# PCB-2__SCH_PHOENIX.net
KiCad netlist of a schematic drawn in EasyEDA
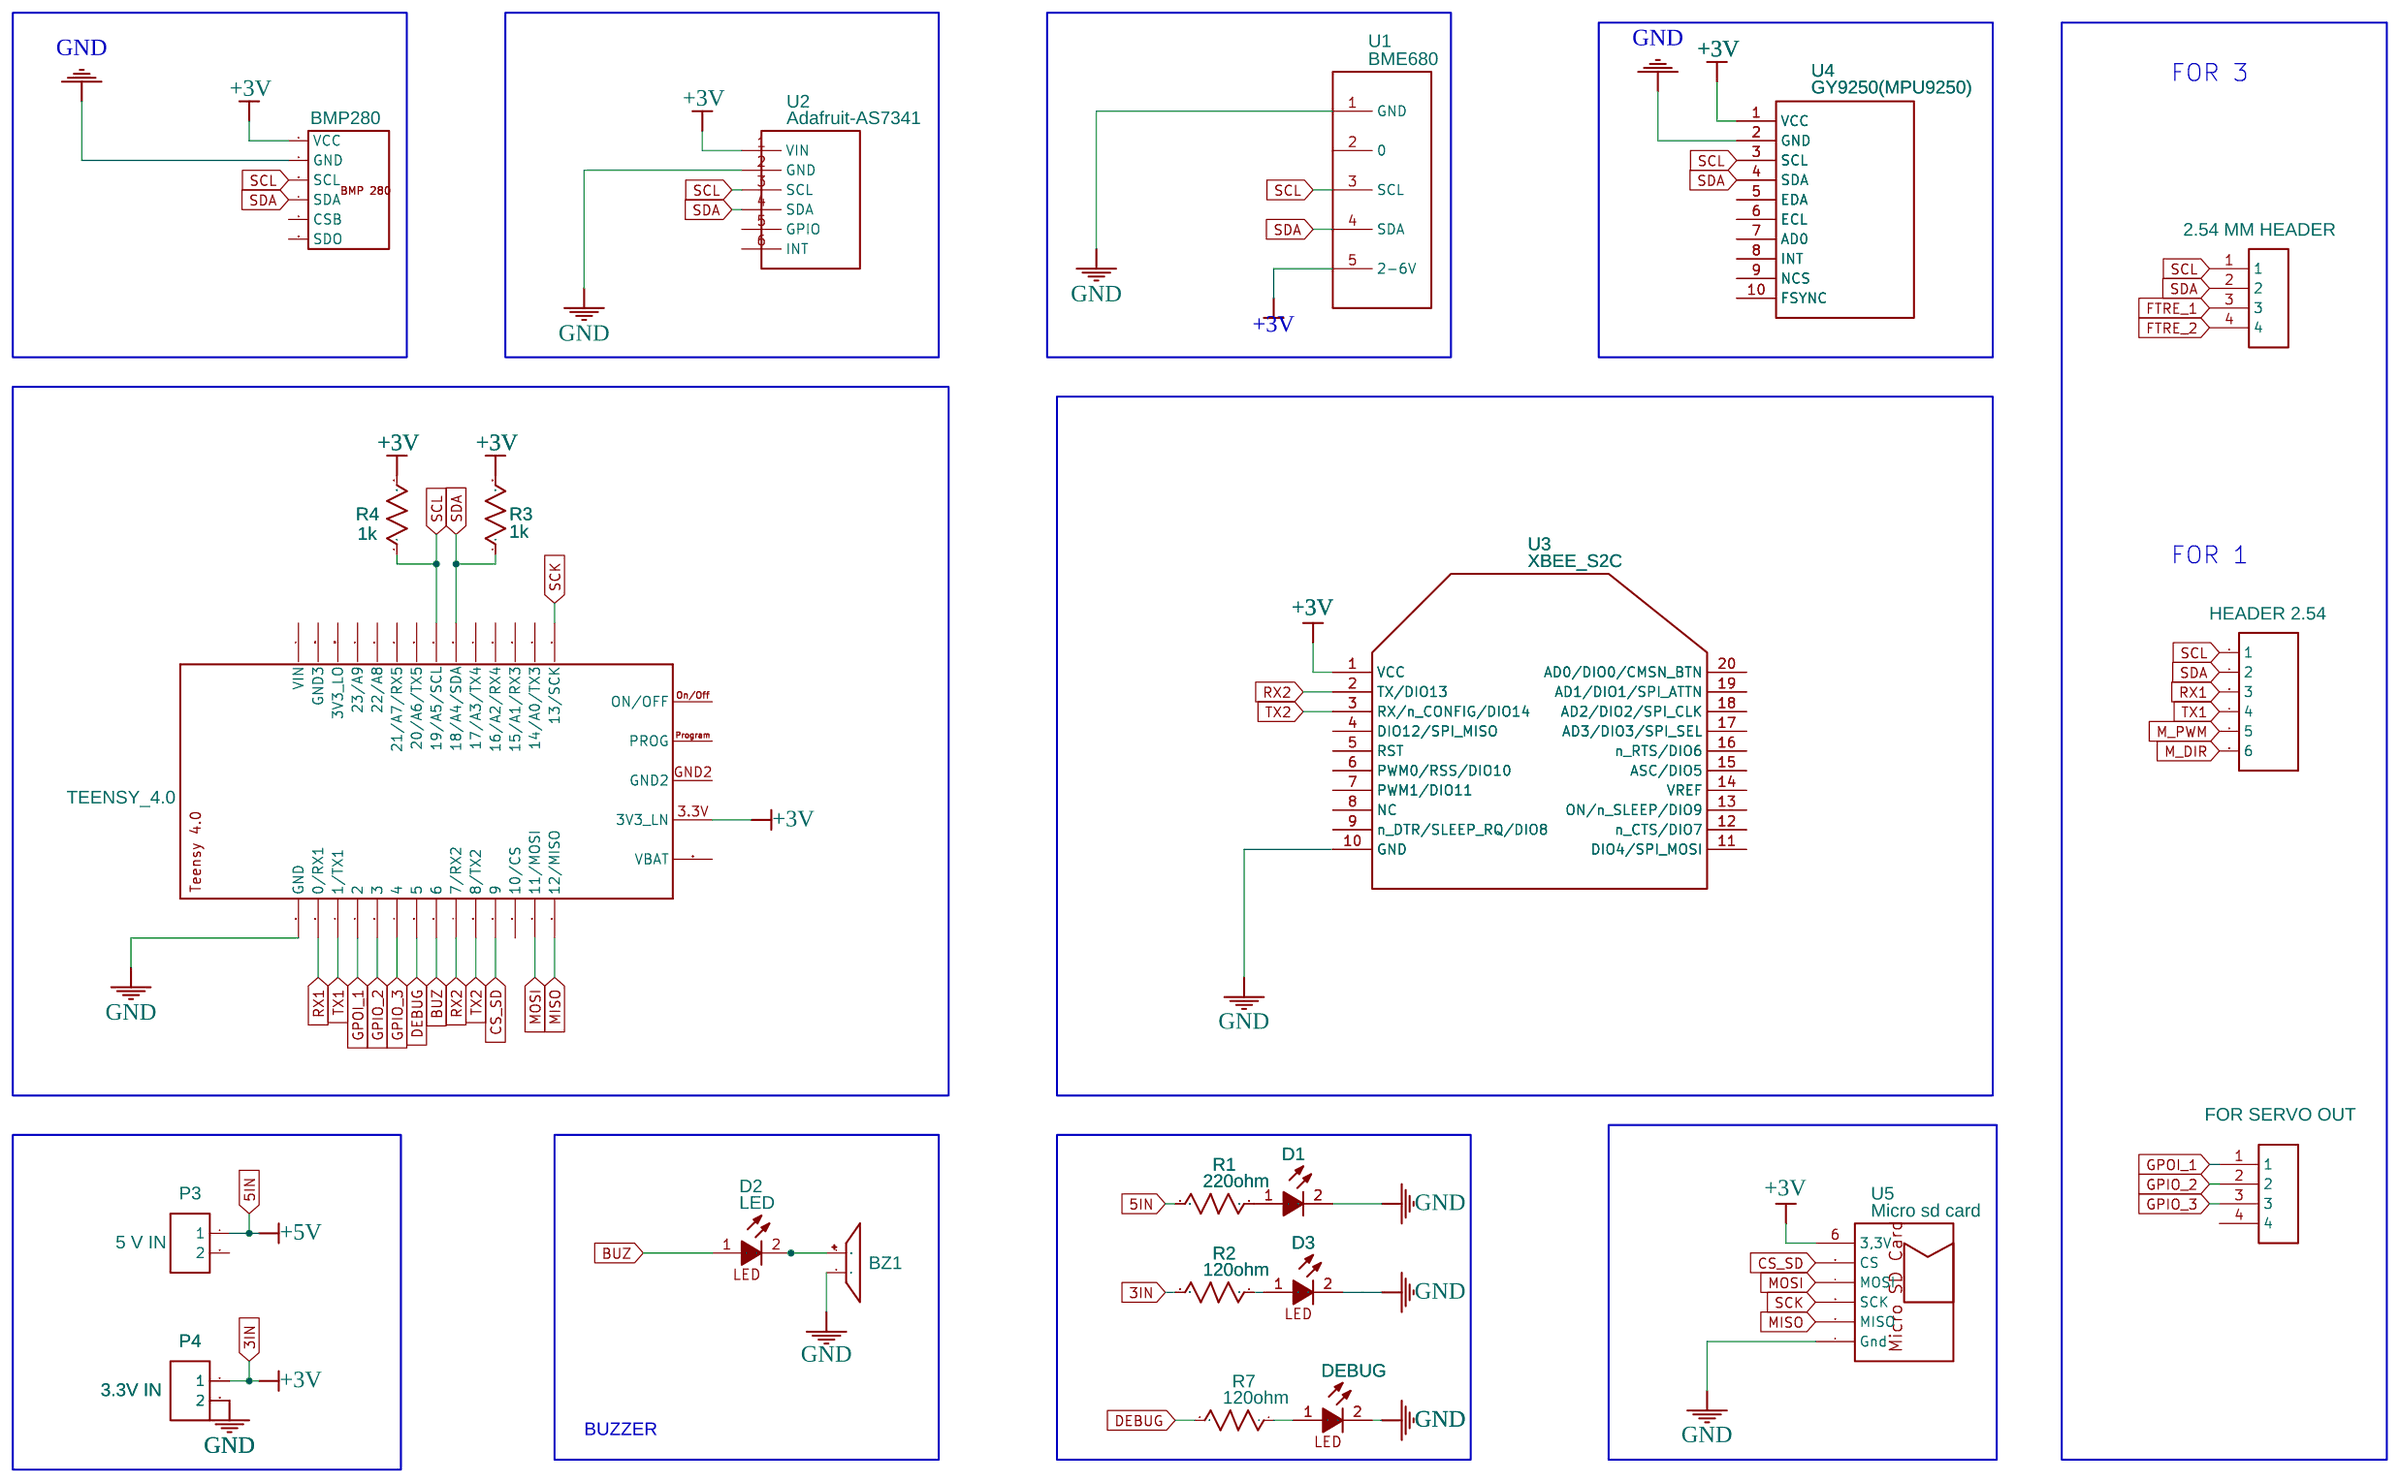
[diagram p0: schematic sheet]

(export (version "E")
  (design (tool "Eeschema 10.0.6"))
  (components
    (comp (ref "0") (value "TEENSY_4.0") (libsource (lib "") (part "TEENSY_4.0")))
    (comp (ref "BZ1") (value "Buzzer") (libsource (lib "") (part "Buzzer")))
    (comp (ref "D1")
      (value "LED")
      (fields (field (name "Manufacturer Part") "5600") (field (name "Manufacturer") "VccLite"))
      (libsource (lib "") (part "LED_1"))
    )
    (comp (ref "D2")
      (value "LED")
      (fields (field (name "Manufacturer Part") "5600") (field (name "Manufacturer") "VccLite"))
      (libsource (lib "") (part "LED_2"))
    )
    (comp (ref "D3")
      (value "LED")
      (fields (field (name "Manufacturer Part") "5600") (field (name "Manufacturer") "VccLite"))
      (libsource (lib "") (part "LED_2"))
    )
    (comp (ref "DEBUG")
      (value "LED")
      (fields (field (name "Manufacturer Part") "5600") (field (name "Manufacturer") "VccLite"))
      (libsource (lib "") (part "LED"))
    )
    (comp (ref "H1")
      (value "2.54 MM HEADER")
      (fields (field (name "Manufacturer Part") "2211S-04G") (field (name "Manufacturer") "MULTICOMP PRO"))
      (libsource (lib "") (part "B2B 2.54 MM HEADER"))
    )
    (comp (ref "H2")
      (value "FOR SERVO OUT")
      (fields (field (name "Manufacturer Part") "2211S-04G") (field (name "Manufacturer") "MULTICOMP PRO"))
      (libsource (lib "") (part "B2B 2.54 MM HEADER"))
    )
    (comp (ref "J1")
      (value "HEADER 2.54")
      (fields (field (name "Manufacturer Part") "2.54mm 1*20PHeader"))
      (libsource (lib "") (part "HEADER-MALE-2.54_1X6"))
    )
    (comp (ref "MOD1") (value "BMP280") (libsource (lib "") (part "BMP280")))
    (comp (ref "P3") (value "5 V IN") (libsource (lib "") (part "CONN-TH_2P-P5.00")))
    (comp (ref "P4") (value "3.3V IN") (libsource (lib "") (part "CONN-TH_2P-P5.00")))
    (comp (ref "R1") (value "220ohm") (libsource (lib "") (part "R_0603_US")))
    (comp (ref "R2") (value "120ohm") (libsource (lib "") (part "R_0603_US")))
    (comp (ref "R3") (value "1k") (libsource (lib "") (part "R_0603_US_1")))
    (comp (ref "R4") (value "1k") (libsource (lib "") (part "R_0603_US_1")))
    (comp (ref "R7") (value "120ohm") (libsource (lib "") (part "R_0603_US")))
    (comp (ref "U1") (value "BME680") (libsource (lib "") (part "BME680")))
    (comp (ref "U2") (value "Adafruit-AS7341") (libsource (lib "") (part "Adafruit-AS7341")))
    (comp (ref "U3")
      (value "XBEE_S2C")
      (fields
        (field (name "Manufacturer Part") "XBP24CZ7PITB003")
        (field (name "Manufacturer") "Digi International")
      )
      (libsource (lib "") (part "XBEE_S2C"))
    )
    (comp (ref "U4") (value "GY9250(MPU9250)") (libsource (lib "") (part "GY9250(MPU9250)")))
    (comp (ref "U5")
      (value "Micro sd card")
      (fields (field (name "Manufacturer Part") "Micro sd card module"))
      (libsource (lib "") (part "Micro sd card module"))
    )
  )
  (nets
    (net (code "1") (name "3IN") (class "Default")
      (node (ref "0") (pin "3.3V") (pinfunction "3V3_LN_3.3V") (pintype "bidirectional"))
      (node (ref "MOD1") (pin "1") (pinfunction "VCC_1") (pintype "unspecified"))
      (node (ref "P4") (pin "1") (pinfunction "1_1") (pintype "unspecified"))
      (node (ref "R2") (pin "2") (pinfunction "2_2") (pintype "unspecified"))
      (node (ref "R3") (pin "2") (pinfunction "2_2") (pintype "unspecified"))
      (node (ref "R4") (pin "2") (pinfunction "2_2") (pintype "unspecified"))
      (node (ref "U1") (pin "5") (pinfunction "2-6V_5") (pintype "passive"))
      (node (ref "U2") (pin "1") (pinfunction "VIN_1") (pintype "unspecified"))
      (node (ref "U3") (pin "1") (pinfunction "VCC_1") (pintype "passive"))
      (node (ref "U4") (pin "1") (pinfunction "VCC_1") (pintype "unspecified"))
      (node (ref "U5") (pin "6") (pinfunction "3,3V_6") (pintype "unspecified"))
    )
    (net (code "2") (name "5IN") (class "Default")
      (node (ref "P3") (pin "1") (pinfunction "1_1") (pintype "unspecified"))
      (node (ref "R1") (pin "2") (pinfunction "2_2") (pintype "unspecified"))
    )
    (net (code "3") (name "BUZ") (class "Default")
      (node (ref "0") (pin "6") (pinfunction "6_6") (pintype "bidirectional"))
      (node (ref "D2") (pin "1") (pinfunction "A_1") (pintype "unspecified"))
    )
    (net (code "4") (name "CS_SD") (class "Default")
      (node (ref "0") (pin "9") (pinfunction "9_9") (pintype "bidirectional"))
      (node (ref "U5") (pin "5") (pinfunction "CS_5") (pintype "unspecified"))
    )
    (net (code "5") (name "DEBUG") (class "Default")
      (node (ref "0") (pin "5") (pinfunction "5_5") (pintype "bidirectional"))
      (node (ref "R7") (pin "2") (pinfunction "2_2") (pintype "unspecified"))
    )
    (net (code "6") (name "FTRE_1") (class "Default")
      (node (ref "H1") (pin "3") (pinfunction "3_3") (pintype "unspecified"))
    )
    (net (code "7") (name "FTRE_2") (class "Default")
      (node (ref "H1") (pin "4") (pinfunction "4_4") (pintype "unspecified"))
    )
    (net (code "8") (name "GND") (class "Default")
      (node (ref "0") (pin "GND1") (pinfunction "GND_GND1") (pintype "bidirectional"))
      (node (ref "BZ1") (pin "2") (pinfunction "2_2") (pintype "unspecified"))
      (node (ref "D1") (pin "2") (pinfunction "K_2") (pintype "unspecified"))
      (node (ref "D3") (pin "2") (pinfunction "K_2") (pintype "unspecified"))
      (node (ref "DEBUG") (pin "2") (pinfunction "K_2") (pintype "unspecified"))
      (node (ref "MOD1") (pin "2") (pinfunction "GND_2") (pintype "unspecified"))
      (node (ref "P4") (pin "2") (pinfunction "2_2") (pintype "unspecified"))
      (node (ref "U1") (pin "1") (pinfunction "GND_1") (pintype "passive"))
      (node (ref "U2") (pin "2") (pinfunction "GND_2") (pintype "unspecified"))
      (node (ref "U3") (pin "10") (pinfunction "GND_10") (pintype "passive"))
      (node (ref "U4") (pin "2") (pinfunction "GND_2") (pintype "unspecified"))
      (node (ref "U5") (pin "1") (pinfunction "Gnd_1") (pintype "unspecified"))
    )
    (net (code "9") (name "GPIO_2") (class "Default")
      (node (ref "0") (pin "3") (pinfunction "3_3") (pintype "bidirectional"))
      (node (ref "H2") (pin "2") (pinfunction "2_2") (pintype "unspecified"))
    )
    (net (code "10") (name "GPIO_3") (class "Default")
      (node (ref "0") (pin "4") (pinfunction "4_4") (pintype "bidirectional"))
      (node (ref "H2") (pin "3") (pinfunction "3_3") (pintype "unspecified"))
    )
    (net (code "11") (name "GPOI_1") (class "Default")
      (node (ref "0") (pin "2") (pinfunction "2_2") (pintype "bidirectional"))
      (node (ref "H2") (pin "1") (pinfunction "1_1") (pintype "unspecified"))
    )
    (net (code "12") (name "MISO") (class "Default")
      (node (ref "0") (pin "12") (pinfunction "12/MISO_12") (pintype "bidirectional"))
      (node (ref "U5") (pin "2") (pinfunction "MISO_2") (pintype "unspecified"))
    )
    (net (code "13") (name "MOSI") (class "Default")
      (node (ref "0") (pin "11") (pinfunction "11/MOSI_11") (pintype "bidirectional"))
      (node (ref "U5") (pin "4") (pinfunction "MOSI_4") (pintype "unspecified"))
    )
    (net (code "14") (name "M_DIR") (class "Default")
      (node (ref "J1") (pin "6") (pinfunction "6_6") (pintype "input"))
    )
    (net (code "15") (name "M_PWM") (class "Default")
      (node (ref "J1") (pin "5") (pinfunction "5_5") (pintype "input"))
    )
    (net (code "16") (name "Net-(BZ1-Buzzer)") (class "Default")
      (node (ref "BZ1") (pin "1") (pinfunction "Buzzer_1") (pintype "unspecified"))
      (node (ref "D2") (pin "2") (pinfunction "K_2") (pintype "unspecified"))
    )
    (net (code "17") (name "Net-(D1-A)") (class "Default")
      (node (ref "D1") (pin "1") (pinfunction "A_1") (pintype "unspecified"))
      (node (ref "R1") (pin "1") (pinfunction "1_1") (pintype "unspecified"))
    )
    (net (code "18") (name "Net-(D3-A)") (class "Default")
      (node (ref "D3") (pin "1") (pinfunction "A_1") (pintype "unspecified"))
      (node (ref "R2") (pin "1") (pinfunction "1_1") (pintype "unspecified"))
    )
    (net (code "19") (name "Net-(DEBUG-A)") (class "Default")
      (node (ref "DEBUG") (pin "1") (pinfunction "A_1") (pintype "unspecified"))
      (node (ref "R7") (pin "1") (pinfunction "1_1") (pintype "unspecified"))
    )
    (net (code "20") (name "RX1") (class "Default")
      (node (ref "0") (pin "0") (pinfunction "0/RX1_0") (pintype "bidirectional"))
      (node (ref "J1") (pin "3") (pinfunction "3_3") (pintype "input"))
    )
    (net (code "21") (name "RX2") (class "Default")
      (node (ref "0") (pin "7") (pinfunction "7/RX2_7") (pintype "bidirectional"))
      (node (ref "U3") (pin "2") (pinfunction "TX/DIO13_2") (pintype "output"))
    )
    (net (code "22") (name "SCK") (class "Default")
      (node (ref "0") (pin "13") (pinfunction "13/SCK_13") (pintype "bidirectional"))
      (node (ref "U5") (pin "3") (pinfunction "SCK_3") (pintype "unspecified"))
    )
    (net (code "23") (name "SCL") (class "Default")
      (node (ref "0") (pin "19") (pinfunction "19/A5/SCL_19") (pintype "bidirectional"))
      (node (ref "H1") (pin "1") (pinfunction "1_1") (pintype "unspecified"))
      (node (ref "J1") (pin "1") (pinfunction "1_1") (pintype "input"))
      (node (ref "MOD1") (pin "3") (pinfunction "SCL_3") (pintype "unspecified"))
      (node (ref "R4") (pin "1") (pinfunction "1_1") (pintype "unspecified"))
      (node (ref "U1") (pin "3") (pinfunction "SCL_3") (pintype "bidirectional"))
      (node (ref "U2") (pin "3") (pinfunction "SCL_3") (pintype "unspecified"))
      (node (ref "U4") (pin "3") (pinfunction "SCL_3") (pintype "unspecified"))
    )
    (net (code "24") (name "SDA") (class "Default")
      (node (ref "0") (pin "18") (pinfunction "18/A4/SDA_18") (pintype "bidirectional"))
      (node (ref "H1") (pin "2") (pinfunction "2_2") (pintype "unspecified"))
      (node (ref "J1") (pin "2") (pinfunction "2_2") (pintype "input"))
      (node (ref "MOD1") (pin "4") (pinfunction "SDA_4") (pintype "unspecified"))
      (node (ref "R3") (pin "1") (pinfunction "1_1") (pintype "unspecified"))
      (node (ref "U1") (pin "4") (pinfunction "SDA_4") (pintype "bidirectional"))
      (node (ref "U2") (pin "4") (pinfunction "SDA_4") (pintype "unspecified"))
      (node (ref "U4") (pin "4") (pinfunction "SDA_4") (pintype "unspecified"))
    )
    (net (code "25") (name "TX1") (class "Default")
      (node (ref "0") (pin "1") (pinfunction "1/TX1_1") (pintype "bidirectional"))
      (node (ref "J1") (pin "4") (pinfunction "4_4") (pintype "input"))
    )
    (net (code "26") (name "TX2") (class "Default")
      (node (ref "0") (pin "8") (pinfunction "8/TX2_8") (pintype "bidirectional"))
      (node (ref "U3") (pin "3") (pinfunction "RX/n_CONFIG/DIO14_3") (pintype "input"))
    )
    (net (code "27") (name "unconnected-(0-3V3_LO-Pad3.3V{slash}250)") (class "Default")
      (node (ref "0") (pin "3.3V/250") (pinfunction "3V3_LO_3.3V/250") (pintype "bidirectional"))
    )
    (net (code "28") (name "unconnected-(0-10{slash}CS-Pad10)") (class "Default")
      (node (ref "0") (pin "10") (pinfunction "10/CS_10") (pintype "bidirectional"))
    )
    (net (code "29") (name "unconnected-(0-14{slash}A0{slash}TX3-Pad14)") (class "Default")
      (node (ref "0") (pin "14") (pinfunction "14/A0/TX3_14") (pintype "bidirectional"))
    )
    (net (code "30") (name "unconnected-(0-15{slash}A1{slash}RX3-Pad15)") (class "Default")
      (node (ref "0") (pin "15") (pinfunction "15/A1/RX3_15") (pintype "bidirectional"))
    )
    (net (code "31") (name "unconnected-(0-16{slash}A2{slash}RX4-Pad16)") (class "Default")
      (node (ref "0") (pin "16") (pinfunction "16/A2/RX4_16") (pintype "bidirectional"))
    )
    (net (code "32") (name "unconnected-(0-17{slash}A3{slash}TX4-Pad17)") (class "Default")
      (node (ref "0") (pin "17") (pinfunction "17/A3/TX4_17") (pintype "bidirectional"))
    )
    (net (code "33") (name "unconnected-(0-20{slash}A6{slash}TX5-Pad20)") (class "Default")
      (node (ref "0") (pin "20") (pinfunction "20/A6/TX5_20") (pintype "bidirectional"))
    )
    (net (code "34") (name "unconnected-(0-21{slash}A7{slash}RX5-Pad21)") (class "Default")
      (node (ref "0") (pin "21") (pinfunction "21/A7/RX5_21") (pintype "bidirectional"))
    )
    (net (code "35") (name "unconnected-(0-22{slash}A8-Pad22)") (class "Default")
      (node (ref "0") (pin "22") (pinfunction "22/A8_22") (pintype "bidirectional"))
    )
    (net (code "36") (name "unconnected-(0-23{slash}A9-Pad23)") (class "Default")
      (node (ref "0") (pin "23") (pinfunction "23/A9_23") (pintype "bidirectional"))
    )
    (net (code "37") (name "unconnected-(0-ON{slash}OFF-PadOn{slash}Off)") (class "Default")
      (node (ref "0") (pin "On/Off") (pinfunction "ON/OFF_On/Off") (pintype "bidirectional"))
    )
    (net (code "38") (name "unconnected-(0-PROG-PadProgram)") (class "Default")
      (node (ref "0") (pin "Program") (pinfunction "PROG_Program") (pintype "bidirectional"))
    )
    (net (code "39") (name "unconnected-(0-PadGND2)") (class "Default")
      (node (ref "0") (pin "GND2") (pinfunction "GND2_GND2") (pintype "bidirectional"))
    )
    (net (code "40") (name "unconnected-(0-PadGND3)") (class "Default")
      (node (ref "0") (pin "GND3") (pinfunction "GND3_GND3") (pintype "bidirectional"))
    )
    (net (code "41") (name "unconnected-(0-PadVIN)") (class "Default")
      (node (ref "0") (pin "VIN") (pinfunction "VIN_VIN") (pintype "bidirectional"))
    )
    (net (code "42") (name "unconnected-(0-VBAT-PadVBat)") (class "Default")
      (node (ref "0") (pin "VBat") (pinfunction "VBAT_VBat") (pintype "bidirectional"))
    )
    (net (code "43") (name "unconnected-(H2-Pad4)") (class "Default")
      (node (ref "H2") (pin "4") (pinfunction "4_4") (pintype "unspecified"))
    )
    (net (code "44") (name "unconnected-(MOD1-CSB-Pad5)") (class "Default")
      (node (ref "MOD1") (pin "5") (pinfunction "CSB_5") (pintype "unspecified"))
    )
    (net (code "45") (name "unconnected-(MOD1-SDO-Pad6)") (class "Default")
      (node (ref "MOD1") (pin "6") (pinfunction "SDO_6") (pintype "unspecified"))
    )
    (net (code "46") (name "unconnected-(P3-Pad2)") (class "Default")
      (node (ref "P3") (pin "2") (pinfunction "2_2") (pintype "unspecified"))
    )
    (net (code "47") (name "unconnected-(U1-0-Pad2)") (class "Default")
      (node (ref "U1") (pin "2") (pinfunction "0_2") (pintype "unspecified"))
    )
    (net (code "48") (name "unconnected-(U2-GPIO-Pad5)") (class "Default")
      (node (ref "U2") (pin "5") (pinfunction "GPIO_5") (pintype "unspecified"))
    )
    (net (code "49") (name "unconnected-(U2-INT-Pad6)") (class "Default")
      (node (ref "U2") (pin "6") (pinfunction "INT_6") (pintype "unspecified"))
    )
    (net (code "50") (name "unconnected-(U3-AD0{slash}DIO0{slash}CMSN_BTN-Pad20)") (class "Default")
      (node (ref "U3") (pin "20") (pinfunction "AD0/DIO0/CMSN_BTN_20") (pintype "input"))
    )
    (net (code "51") (name "unconnected-(U3-AD1{slash}DIO1{slash}SPI_ATTN-Pad19)") (class "Default")
      (node (ref "U3") (pin "19") (pinfunction "AD1/DIO1/SPI_ATTN_19") (pintype "bidirectional"))
    )
    (net (code "52") (name "unconnected-(U3-AD2{slash}DIO2{slash}SPI_CLK-Pad18)") (class "Default")
      (node (ref "U3") (pin "18") (pinfunction "AD2/DIO2/SPI_CLK_18") (pintype "bidirectional"))
    )
    (net (code "53") (name "unconnected-(U3-AD3{slash}DIO3{slash}SPI_SEL-Pad17)") (class "Default")
      (node (ref "U3") (pin "17") (pinfunction "AD3/DIO3/SPI_SEL_17") (pintype "bidirectional"))
    )
    (net (code "54") (name "unconnected-(U3-ASC{slash}DIO5-Pad15)") (class "Default")
      (node (ref "U3") (pin "15") (pinfunction "ASC/DIO5_15") (pintype "input"))
    )
    (net (code "55") (name "unconnected-(U3-DIO4{slash}SPI_MOSI-Pad11)") (class "Default")
      (node (ref "U3") (pin "11") (pinfunction "DIO4/SPI_MOSI_11") (pintype "input"))
    )
    (net (code "56") (name "unconnected-(U3-DIO12{slash}SPI_MISO-Pad4)") (class "Default")
      (node (ref "U3") (pin "4") (pinfunction "DIO12/SPI_MISO_4") (pintype "bidirectional"))
    )
    (net (code "57") (name "unconnected-(U3-NC-Pad8)") (class "Default")
      (node (ref "U3") (pin "8") (pinfunction "NC_8") (pintype "input"))
    )
    (net (code "58") (name "unconnected-(U3-ON{slash}n_SLEEP{slash}DIO9-Pad13)") (class "Default")
      (node (ref "U3") (pin "13") (pinfunction "ON/n_SLEEP/DIO9_13") (pintype "bidirectional"))
    )
    (net (code "59") (name "unconnected-(U3-PWM0{slash}RSS{slash}DIO10-Pad6)") (class "Default")
      (node (ref "U3") (pin "6") (pinfunction "PWM0/RSS/DIO10_6") (pintype "input"))
    )
    (net (code "60") (name "unconnected-(U3-PWM1{slash}DIO11-Pad7)") (class "Default")
      (node (ref "U3") (pin "7") (pinfunction "PWM1/DIO11_7") (pintype "input"))
    )
    (net (code "61") (name "unconnected-(U3-RST-Pad5)") (class "Default")
      (node (ref "U3") (pin "5") (pinfunction "RST_5") (pintype "input"))
    )
    (net (code "62") (name "unconnected-(U3-VREF-Pad14)") (class "Default")
      (node (ref "U3") (pin "14") (pinfunction "VREF_14") (pintype "input"))
    )
    (net (code "63") (name "unconnected-(U3-n_CTS{slash}DIO7-Pad12)") (class "Default")
      (node (ref "U3") (pin "12") (pinfunction "n_CTS/DIO7_12") (pintype "unspecified"))
    )
    (net (code "64") (name "unconnected-(U3-n_DTR{slash}SLEEP_RQ{slash}DIO8-Pad9)") (class "Default")
      (node (ref "U3") (pin "9") (pinfunction "n_DTR/SLEEP_RQ/DIO8_9") (pintype "bidirectional"))
    )
    (net (code "65") (name "unconnected-(U3-n_RTS{slash}DIO6-Pad16)") (class "Default")
      (node (ref "U3") (pin "16") (pinfunction "n_RTS/DIO6_16") (pintype "bidirectional"))
    )
    (net (code "66") (name "unconnected-(U4-AD0-Pad7)") (class "Default")
      (node (ref "U4") (pin "7") (pinfunction "AD0_7") (pintype "unspecified"))
    )
    (net (code "67") (name "unconnected-(U4-ECL-Pad6)") (class "Default")
      (node (ref "U4") (pin "6") (pinfunction "ECL_6") (pintype "unspecified"))
    )
    (net (code "68") (name "unconnected-(U4-EDA-Pad5)") (class "Default")
      (node (ref "U4") (pin "5") (pinfunction "EDA_5") (pintype "unspecified"))
    )
    (net (code "69") (name "unconnected-(U4-FSYNC-Pad10)") (class "Default")
      (node (ref "U4") (pin "10") (pinfunction "FSYNC_10") (pintype "unspecified"))
    )
    (net (code "70") (name "unconnected-(U4-INT-Pad8)") (class "Default")
      (node (ref "U4") (pin "8") (pinfunction "INT_8") (pintype "unspecified"))
    )
    (net (code "71") (name "unconnected-(U4-NCS-Pad9)") (class "Default")
      (node (ref "U4") (pin "9") (pinfunction "NCS_9") (pintype "unspecified"))
    )
  )
)
